# 3_MG32F003_QFN20.net
KiCad netlist of a schematic drawn in Altium Designer
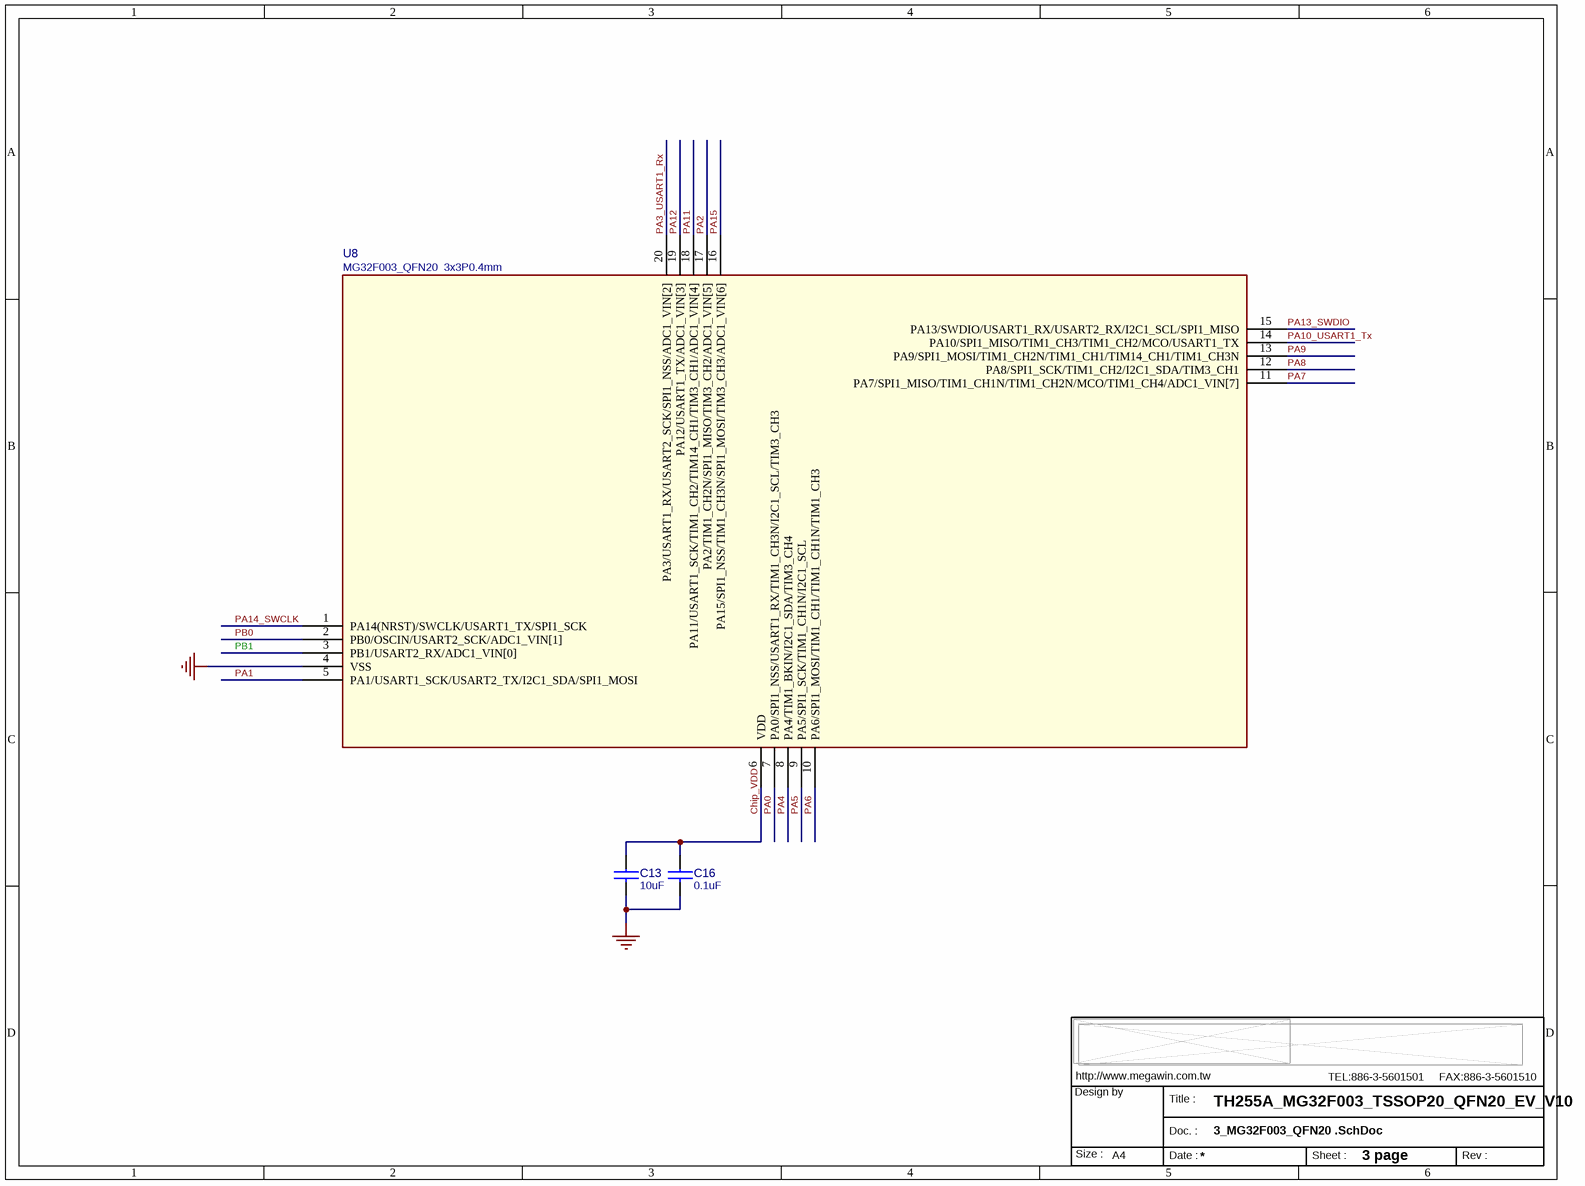
[diagram p0: 3_MG32F003_QFN20 .SchDoc]

(export (version "E")
  (design (tool "Eeschema 10.0.6"))
  (components
    (comp (ref "C13") (value "10uF") (footprint "C-0603") (libsource (lib "*") (part "CAP NP_Dup1")))
    (comp (ref "C16") (value "0.1uF") (footprint "C-0603") (libsource (lib "*") (part "CAP NP_Dup1")))
    (comp (ref "MW1")
      (value "MW-A4")
      (footprint "MEGAWIN_3.4")
      (fields
        (field (name "ORGADDR2") "http://www.megawin.com.tw")
        (field (name "ORGADDR3") "TEL:886-3-5601501     FAX:886-3-5601510")
      )
      (libsource (lib "201407_SCHLIB") (part "MW_A4_2"))
    )
    (comp (ref "U8")
      (value "MG32F003_QFN20  3x3P0.4mm")
      (footprint "QFN20_3X3P040_1")
      (libsource (lib "*") (part "MG32F003_QFN20"))
    )
  )
  (nets
    (net (code "1") (name "/Chip_VDD") (class "Default")
      (node (ref "C13") (pin "1") (pinfunction "1_1") (pintype "passive"))
      (node (ref "C16") (pin "1") (pinfunction "1_1") (pintype "passive"))
      (node (ref "U8") (pin "6") (pinfunction "VDD_6") (pintype "passive"))
    )
    (net (code "2") (name "/PA0") (class "Default")
      (node (ref "U8") (pin "7") (pinfunction "PA0/SPI1_NSS/USART1_RX/TIM1_CH3N/I2C1_SCL/TIM3_CH3_7") (pintype "passive"))
    )
    (net (code "3") (name "/PA1") (class "Default")
      (node (ref "U8") (pin "5") (pinfunction "PA1/USART1_SCK/USART2_TX/I2C1_SDA/SPI1_MOSI_5") (pintype "passive"))
    )
    (net (code "4") (name "/PA2") (class "Default")
      (node (ref "U8") (pin "17") (pinfunction "PA2/TIM1_CH2N/SPI1_MISO/TIM3_CH2/ADC1_VIN[5]_17") (pintype "passive"))
    )
    (net (code "5") (name "/PA3_USART1_Rx") (class "Default")
      (node (ref "U8") (pin "20") (pinfunction "PA3/USART1_RX/USART2_SCK/SPI1_NSS/ADC1_VIN[2]_20") (pintype "passive"))
    )
    (net (code "6") (name "/PA4") (class "Default")
      (node (ref "U8") (pin "8") (pinfunction "PA4/TIM1_BKIN/I2C1_SDA/TIM3_CH4_8") (pintype "passive"))
    )
    (net (code "7") (name "/PA5") (class "Default")
      (node (ref "U8") (pin "9") (pinfunction "PA5/SPI1_SCK/TIM1_CH1N/I2C1_SCL_9") (pintype "passive"))
    )
    (net (code "8") (name "/PA6") (class "Default")
      (node (ref "U8") (pin "10") (pinfunction "PA6/SPI1_MOSI/TIM1_CH1/TIM1_CH1N/TIM1_CH3_10") (pintype "passive"))
    )
    (net (code "9") (name "/PA7") (class "Default")
      (node (ref "U8") (pin "11") (pinfunction "PA7/SPI1_MISO/TIM1_CH1N/TIM1_CH2N/MCO/TIM1_CH4/ADC1_VIN[7]_11") (pintype "passive"))
    )
    (net (code "10") (name "/PA8") (class "Default")
      (node (ref "U8") (pin "12") (pinfunction "PA8/SPI1_SCK/TIM1_CH2/I2C1_SDA/TIM3_CH1_12") (pintype "passive"))
    )
    (net (code "11") (name "/PA9") (class "Default")
      (node (ref "U8") (pin "13") (pinfunction "PA9/SPI1_MOSI/TIM1_CH2N/TIM1_CH1/TIM14_CH1/TIM1_CH3N_13") (pintype "passive"))
    )
    (net (code "12") (name "/PA10_USART1_Tx") (class "Default")
      (node (ref "U8") (pin "14") (pinfunction "PA10/SPI1_MISO/TIM1_CH3/TIM1_CH2/MCO/USART1_TX_14") (pintype "passive"))
    )
    (net (code "13") (name "/PA11") (class "Default")
      (node (ref "U8") (pin "18") (pinfunction "PA11/USART1_SCK/TIM1_CH2/TIM14_CH1/TIM3_CH1/ADC1_VIN[4]_18") (pintype "passive"))
    )
    (net (code "14") (name "/PA12") (class "Default")
      (node (ref "U8") (pin "19") (pinfunction "PA12/USART1_TX/ADC1_VIN[3]_19") (pintype "passive"))
    )
    (net (code "15") (name "/PA13_SWDIO") (class "Default")
      (node (ref "U8") (pin "15") (pinfunction "PA13/SWDIO/USART1_RX/USART2_RX/I2C1_SCL/SPI1_MISO_15") (pintype "passive"))
    )
    (net (code "16") (name "/PA14_SWCLK") (class "Default")
      (node (ref "U8") (pin "1") (pinfunction "PA14(NRST)/SWCLK/USART1_TX/SPI1_SCK_1") (pintype "passive"))
    )
    (net (code "17") (name "/PA15") (class "Default")
      (node (ref "U8") (pin "16") (pinfunction "PA15/SPI1_NSS/TIM1_CH3N/SPI1_MOSI/TIM3_CH3/ADC1_VIN[6]_16") (pintype "passive"))
    )
    (net (code "18") (name "/PB0") (class "Default")
      (node (ref "U8") (pin "2") (pinfunction "PB0/OSCIN/USART2_SCK/ADC1_VIN[1]_2") (pintype "passive"))
    )
    (net (code "19") (name "/PB1") (class "Default")
      (node (ref "U8") (pin "3") (pinfunction "PB1/USART2_RX/ADC1_VIN[0]_3") (pintype "passive"))
    )
    (net (code "20") (name "GND_POWER") (class "Default")
      (node (ref "C13") (pin "2") (pinfunction "2_2") (pintype "passive"))
      (node (ref "C16") (pin "2") (pinfunction "2_2") (pintype "passive"))
      (node (ref "U8") (pin "4") (pinfunction "VSS_4") (pintype "passive"))
    )
  )
)
